# I2C_iso_mini_v30.net
KiCad netlist of a schematic drawn in EAGLE
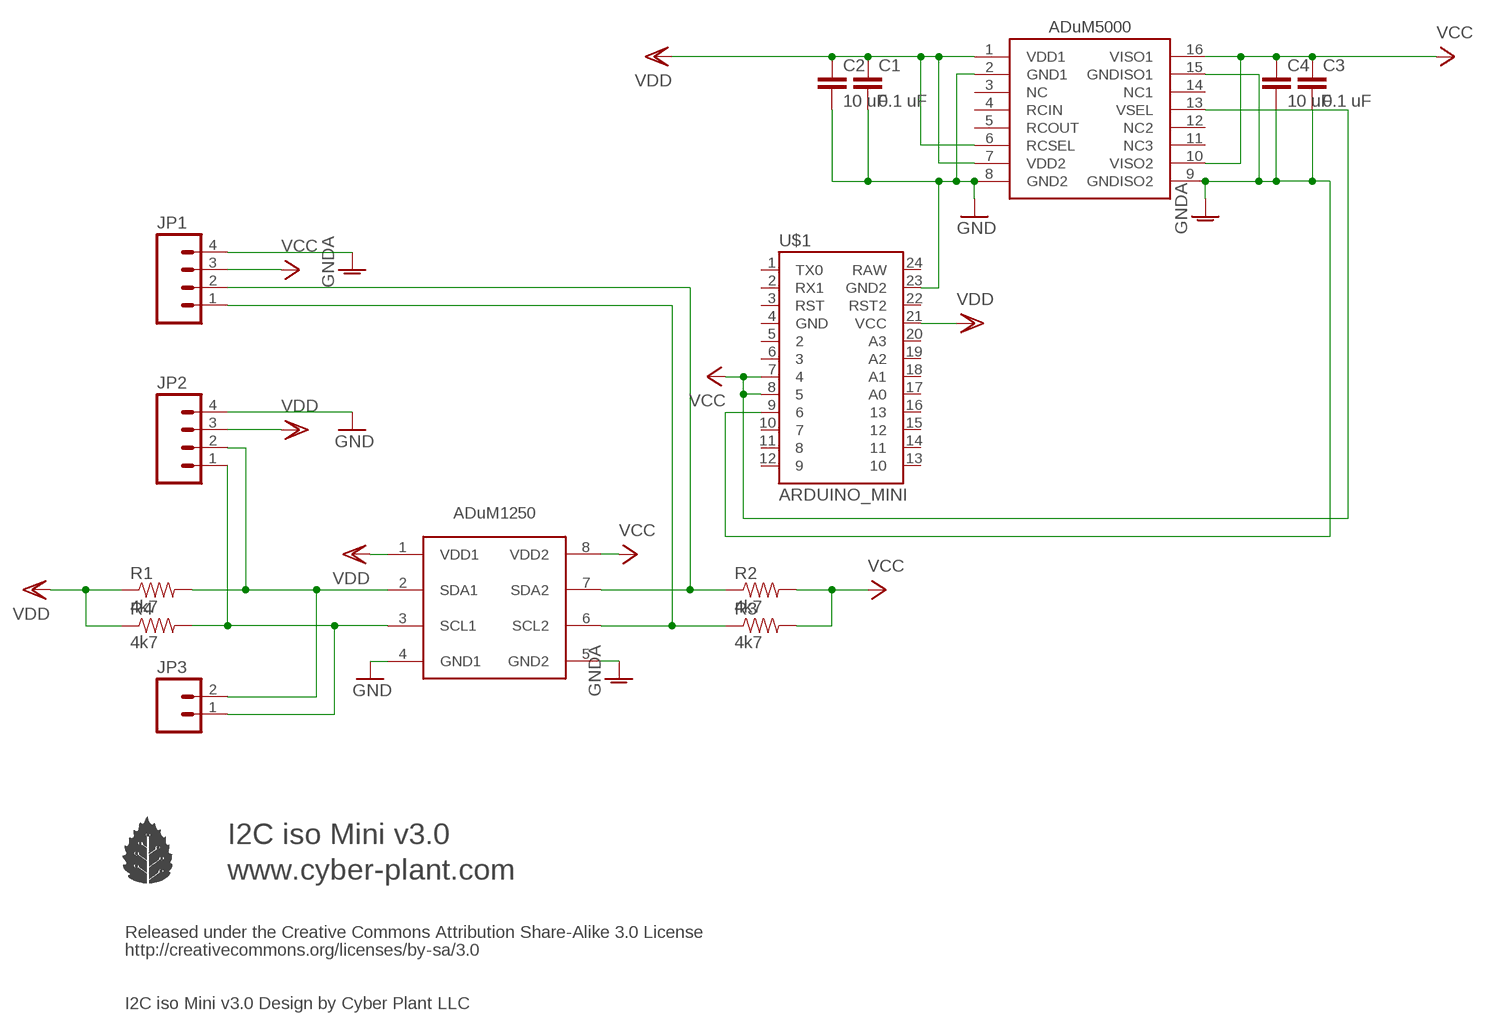
[diagram p0: schematic, sheet 1]

(export (version "E")
  (design (tool "Eeschema 10.0.6"))
  (components
    (comp (ref "C1")
      (value "0.1 uF")
      (footprint "eagle-import:1206")
      (libsource (lib "eagle-import") (part "CAP1206"))
    )
    (comp (ref "C2")
      (value "10 uF")
      (footprint "eagle-import:1206")
      (libsource (lib "eagle-import") (part "CAP1206"))
    )
    (comp (ref "C3")
      (value "0.1 uF")
      (footprint "eagle-import:1206")
      (libsource (lib "eagle-import") (part "CAP1206"))
    )
    (comp (ref "C4")
      (value "10 uF")
      (footprint "eagle-import:1206")
      (libsource (lib "eagle-import") (part "CAP1206"))
    )
    (comp (ref "JP1")
      (value "M04PTH")
      (footprint "eagle-import:1X04")
      (libsource (lib "eagle-import") (part "M04PTH"))
    )
    (comp (ref "JP2")
      (value "M04PTH")
      (footprint "eagle-import:1X04")
      (libsource (lib "eagle-import") (part "M04PTH"))
    )
    (comp (ref "JP3")
      (value "M02PTH")
      (footprint "eagle-import:1X02")
      (libsource (lib "eagle-import") (part "M02PTH"))
    )
    (comp (ref "R1")
      (value "4k7")
      (footprint "eagle-import:1206")
      (libsource (lib "eagle-import") (part "RESISTOR1206"))
    )
    (comp (ref "R2")
      (value "4k7")
      (footprint "eagle-import:1206")
      (libsource (lib "eagle-import") (part "RESISTOR1206"))
    )
    (comp (ref "R3")
      (value "4k7")
      (footprint "eagle-import:1206")
      (libsource (lib "eagle-import") (part "RESISTOR1206"))
    )
    (comp (ref "R4")
      (value "4k7")
      (footprint "eagle-import:1206")
      (libsource (lib "eagle-import") (part "RESISTOR1206"))
    )
    (comp (ref "U$1")
      (value "ARDUINO_MINI")
      (footprint "eagle-import:ARDUINO_MINI")
      (libsource (lib "eagle-import") (part "ARDUINO_MINI"))
    )
    (comp (ref "U$3")
      (value "ADUM1251")
      (footprint "eagle-import:SO8")
      (libsource (lib "eagle-import") (part "ADUM1251"))
    )
    (comp (ref "U$4")
      (value "ADUM5000")
      (footprint "eagle-import:SO-16W")
      (libsource (lib "eagle-import") (part "ADUM5000"))
    )
  )
  (nets
    (net (code "1") (name "GND") (class "Default")
      (node (ref "C1") (pin "2") (pinfunction "2_2") (pintype "passive"))
      (node (ref "C2") (pin "2") (pinfunction "2_2") (pintype "passive"))
      (node (ref "JP2") (pin "4") (pinfunction "4_4") (pintype "passive"))
      (node (ref "U$1") (pin "23") (pinfunction "GND2_23") (pintype "bidirectional"))
      (node (ref "U$3") (pin "4") (pinfunction "GND1_4") (pintype "bidirectional"))
      (node (ref "U$4") (pin "2") (pinfunction "GND1_2") (pintype "bidirectional"))
      (node (ref "U$4") (pin "8") (pinfunction "GND2_8") (pintype "bidirectional"))
    )
    (net (code "2") (name "GNDA") (class "Default")
      (node (ref "C3") (pin "2") (pinfunction "2_2") (pintype "passive"))
      (node (ref "C4") (pin "2") (pinfunction "2_2") (pintype "passive"))
      (node (ref "JP1") (pin "4") (pinfunction "4_4") (pintype "passive"))
      (node (ref "U$1") (pin "9") (pinfunction "6_9") (pintype "bidirectional"))
      (node (ref "U$3") (pin "5") (pinfunction "GND2_5") (pintype "bidirectional"))
      (node (ref "U$4") (pin "15") (pinfunction "GNDISO1_15") (pintype "bidirectional"))
      (node (ref "U$4") (pin "9") (pinfunction "GNDISO2_9") (pintype "bidirectional"))
    )
    (net (code "3") (name "Net-(U$3-SCL1)") (class "Default")
      (node (ref "JP2") (pin "1") (pinfunction "1_1") (pintype "passive"))
      (node (ref "JP3") (pin "1") (pinfunction "1_1") (pintype "passive"))
      (node (ref "R4") (pin "2") (pinfunction "2_2") (pintype "passive"))
      (node (ref "U$3") (pin "3") (pinfunction "SCL1_3") (pintype "bidirectional"))
    )
    (net (code "4") (name "Net-(U$3-SCL2)") (class "Default")
      (node (ref "JP1") (pin "1") (pinfunction "1_1") (pintype "passive"))
      (node (ref "R3") (pin "1") (pinfunction "1_1") (pintype "passive"))
      (node (ref "U$3") (pin "6") (pinfunction "SCL2_6") (pintype "bidirectional"))
    )
    (net (code "5") (name "Net-(U$3-SDA1)") (class "Default")
      (node (ref "JP2") (pin "2") (pinfunction "2_2") (pintype "passive"))
      (node (ref "JP3") (pin "2") (pinfunction "2_2") (pintype "passive"))
      (node (ref "R1") (pin "2") (pinfunction "2_2") (pintype "passive"))
      (node (ref "U$3") (pin "2") (pinfunction "SDA1_2") (pintype "bidirectional"))
    )
    (net (code "6") (name "Net-(U$3-SDA2)") (class "Default")
      (node (ref "JP1") (pin "2") (pinfunction "2_2") (pintype "passive"))
      (node (ref "R2") (pin "1") (pinfunction "1_1") (pintype "passive"))
      (node (ref "U$3") (pin "7") (pinfunction "SDA2_7") (pintype "bidirectional"))
    )
    (net (code "7") (name "VCC") (class "Default")
      (node (ref "C3") (pin "1") (pinfunction "1_1") (pintype "passive"))
      (node (ref "C4") (pin "1") (pinfunction "1_1") (pintype "passive"))
      (node (ref "JP1") (pin "3") (pinfunction "3_3") (pintype "passive"))
      (node (ref "R2") (pin "2") (pinfunction "2_2") (pintype "passive"))
      (node (ref "R3") (pin "2") (pinfunction "2_2") (pintype "passive"))
      (node (ref "U$1") (pin "7") (pinfunction "4_7") (pintype "bidirectional"))
      (node (ref "U$1") (pin "8") (pinfunction "5_8") (pintype "bidirectional"))
      (node (ref "U$3") (pin "8") (pinfunction "VDD2_8") (pintype "bidirectional"))
      (node (ref "U$4") (pin "10") (pinfunction "VISO2_10") (pintype "bidirectional"))
      (node (ref "U$4") (pin "13") (pinfunction "VSEL_13") (pintype "output"))
      (node (ref "U$4") (pin "16") (pinfunction "VISO1_16") (pintype "bidirectional"))
    )
    (net (code "8") (name "VDD") (class "Default")
      (node (ref "C1") (pin "1") (pinfunction "1_1") (pintype "passive"))
      (node (ref "C2") (pin "1") (pinfunction "1_1") (pintype "passive"))
      (node (ref "JP2") (pin "3") (pinfunction "3_3") (pintype "passive"))
      (node (ref "R1") (pin "1") (pinfunction "1_1") (pintype "passive"))
      (node (ref "R4") (pin "1") (pinfunction "1_1") (pintype "passive"))
      (node (ref "U$1") (pin "21") (pinfunction "VCC_21") (pintype "bidirectional"))
      (node (ref "U$3") (pin "1") (pinfunction "VDD1_1") (pintype "bidirectional"))
      (node (ref "U$4") (pin "1") (pinfunction "VDD1_1") (pintype "bidirectional"))
      (node (ref "U$4") (pin "6") (pinfunction "RCSEL_6") (pintype "input"))
      (node (ref "U$4") (pin "7") (pinfunction "VDD2_7") (pintype "bidirectional"))
    )
    (net (code "9") (name "unconnected-(U$1-2-Pad5)") (class "Default")
      (node (ref "U$1") (pin "5") (pinfunction "2_5") (pintype "bidirectional"))
    )
    (net (code "10") (name "unconnected-(U$1-3-Pad6)") (class "Default")
      (node (ref "U$1") (pin "6") (pinfunction "3_6") (pintype "bidirectional"))
    )
    (net (code "11") (name "unconnected-(U$1-7-Pad10)") (class "Default")
      (node (ref "U$1") (pin "10") (pinfunction "7_10") (pintype "bidirectional"))
    )
    (net (code "12") (name "unconnected-(U$1-8-Pad11)") (class "Default")
      (node (ref "U$1") (pin "11") (pinfunction "8_11") (pintype "bidirectional"))
    )
    (net (code "13") (name "unconnected-(U$1-9-Pad12)") (class "Default")
      (node (ref "U$1") (pin "12") (pinfunction "9_12") (pintype "bidirectional"))
    )
    (net (code "14") (name "unconnected-(U$1-10-Pad13)") (class "Default")
      (node (ref "U$1") (pin "13") (pinfunction "10_13") (pintype "bidirectional"))
    )
    (net (code "15") (name "unconnected-(U$1-11-Pad14)") (class "Default")
      (node (ref "U$1") (pin "14") (pinfunction "11_14") (pintype "bidirectional"))
    )
    (net (code "16") (name "unconnected-(U$1-12-Pad15)") (class "Default")
      (node (ref "U$1") (pin "15") (pinfunction "12_15") (pintype "bidirectional"))
    )
    (net (code "17") (name "unconnected-(U$1-13-Pad16)") (class "Default")
      (node (ref "U$1") (pin "16") (pinfunction "13_16") (pintype "bidirectional"))
    )
    (net (code "18") (name "unconnected-(U$1-A0-Pad17)") (class "Default")
      (node (ref "U$1") (pin "17") (pinfunction "A0_17") (pintype "bidirectional"))
    )
    (net (code "19") (name "unconnected-(U$1-A1-Pad18)") (class "Default")
      (node (ref "U$1") (pin "18") (pinfunction "A1_18") (pintype "bidirectional"))
    )
    (net (code "20") (name "unconnected-(U$1-A2-Pad19)") (class "Default")
      (node (ref "U$1") (pin "19") (pinfunction "A2_19") (pintype "bidirectional"))
    )
    (net (code "21") (name "unconnected-(U$1-A3-Pad20)") (class "Default")
      (node (ref "U$1") (pin "20") (pinfunction "A3_20") (pintype "bidirectional"))
    )
    (net (code "22") (name "unconnected-(U$1-GND-Pad4)") (class "Default")
      (node (ref "U$1") (pin "4") (pinfunction "GND_4") (pintype "bidirectional"))
    )
    (net (code "23") (name "unconnected-(U$1-RAW-Pad24)") (class "Default")
      (node (ref "U$1") (pin "24") (pinfunction "RAW_24") (pintype "bidirectional"))
    )
    (net (code "24") (name "unconnected-(U$1-RST-Pad3)") (class "Default")
      (node (ref "U$1") (pin "3") (pinfunction "RST_3") (pintype "bidirectional"))
    )
    (net (code "25") (name "unconnected-(U$1-RST2-Pad22)") (class "Default")
      (node (ref "U$1") (pin "22") (pinfunction "RST2_22") (pintype "bidirectional"))
    )
    (net (code "26") (name "unconnected-(U$1-RX1-Pad2)") (class "Default")
      (node (ref "U$1") (pin "2") (pinfunction "RX1_2") (pintype "bidirectional"))
    )
    (net (code "27") (name "unconnected-(U$1-TX0-Pad1)") (class "Default")
      (node (ref "U$1") (pin "1") (pinfunction "TX0_1") (pintype "bidirectional"))
    )
    (net (code "28") (name "unconnected-(U$4-NC-Pad3)") (class "Default")
      (node (ref "U$4") (pin "3") (pinfunction "NC_3") (pintype "no_connect"))
    )
    (net (code "29") (name "unconnected-(U$4-NC1-Pad14)") (class "Default")
      (node (ref "U$4") (pin "14") (pinfunction "NC1_14") (pintype "no_connect"))
    )
    (net (code "30") (name "unconnected-(U$4-NC2-Pad12)") (class "Default")
      (node (ref "U$4") (pin "12") (pinfunction "NC2_12") (pintype "no_connect"))
    )
    (net (code "31") (name "unconnected-(U$4-NC3-Pad11)") (class "Default")
      (node (ref "U$4") (pin "11") (pinfunction "NC3_11") (pintype "no_connect"))
    )
    (net (code "32") (name "unconnected-(U$4-RCIN-Pad4)") (class "Default")
      (node (ref "U$4") (pin "4") (pinfunction "RCIN_4") (pintype "input"))
    )
    (net (code "33") (name "unconnected-(U$4-RCOUT-Pad5)") (class "Default")
      (node (ref "U$4") (pin "5") (pinfunction "RCOUT_5") (pintype "output"))
    )
  )
)
